# BMS_Schematic.net
KiCad netlist of a schematic drawn in EAGLE
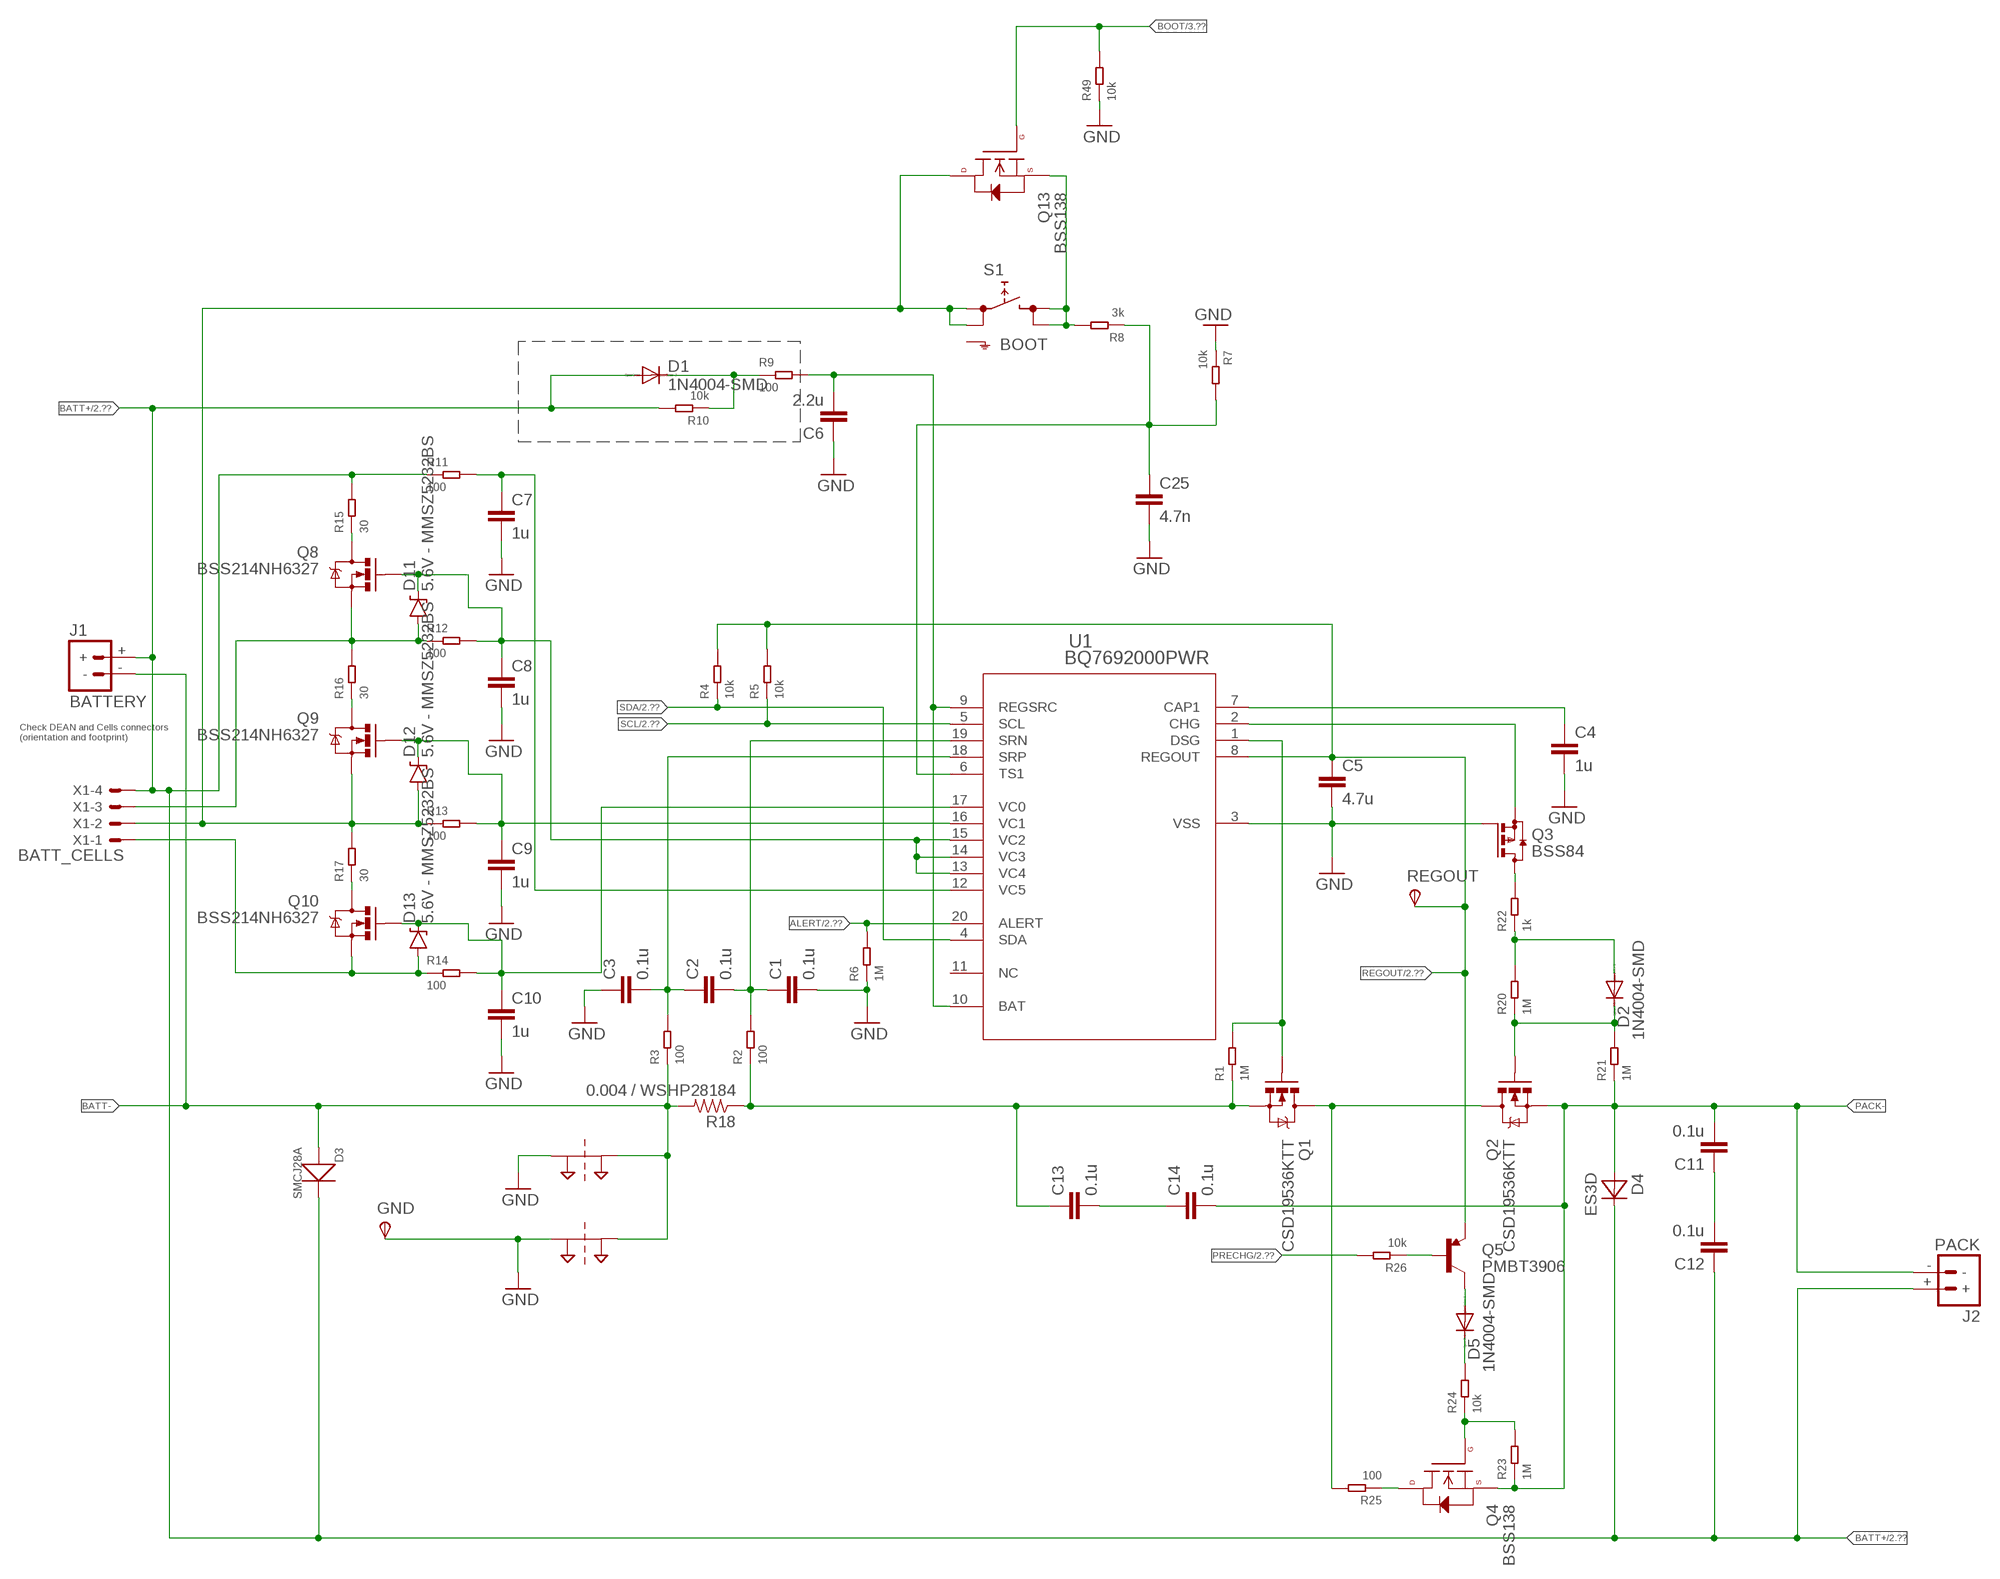
[diagram p0: schematic, sheet 1]
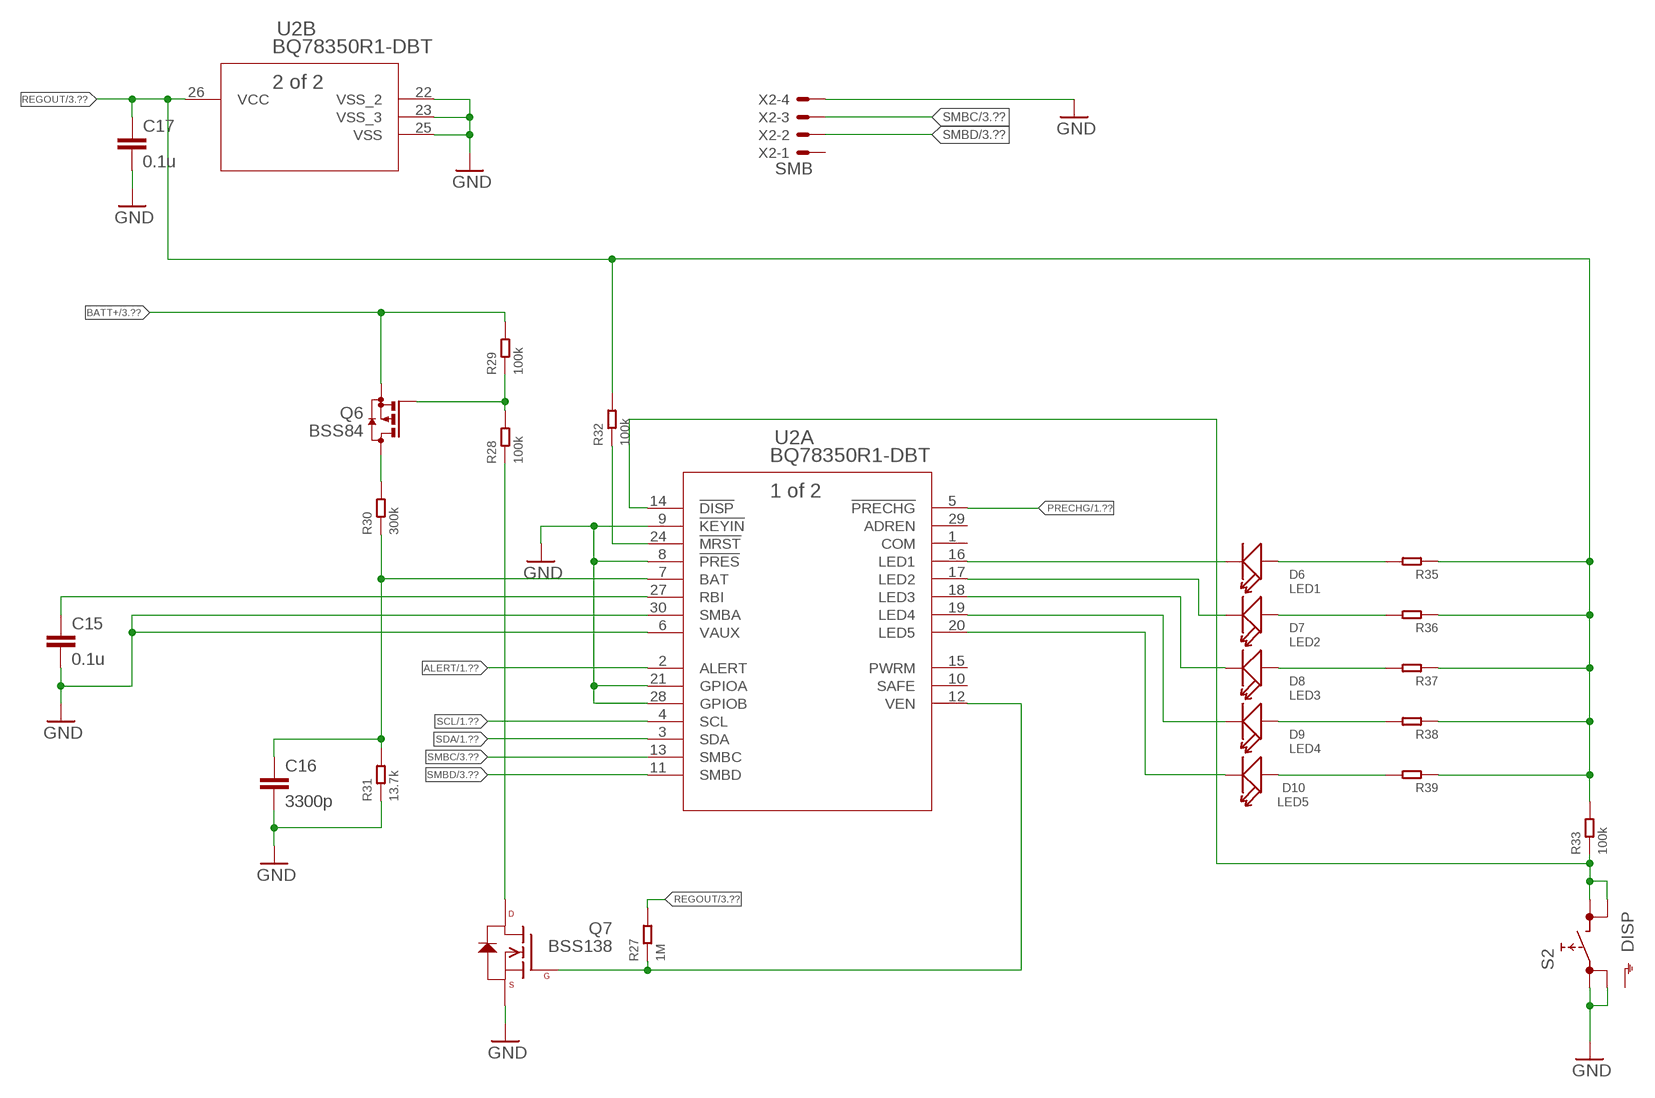
[diagram p1: schematic, sheet 2]
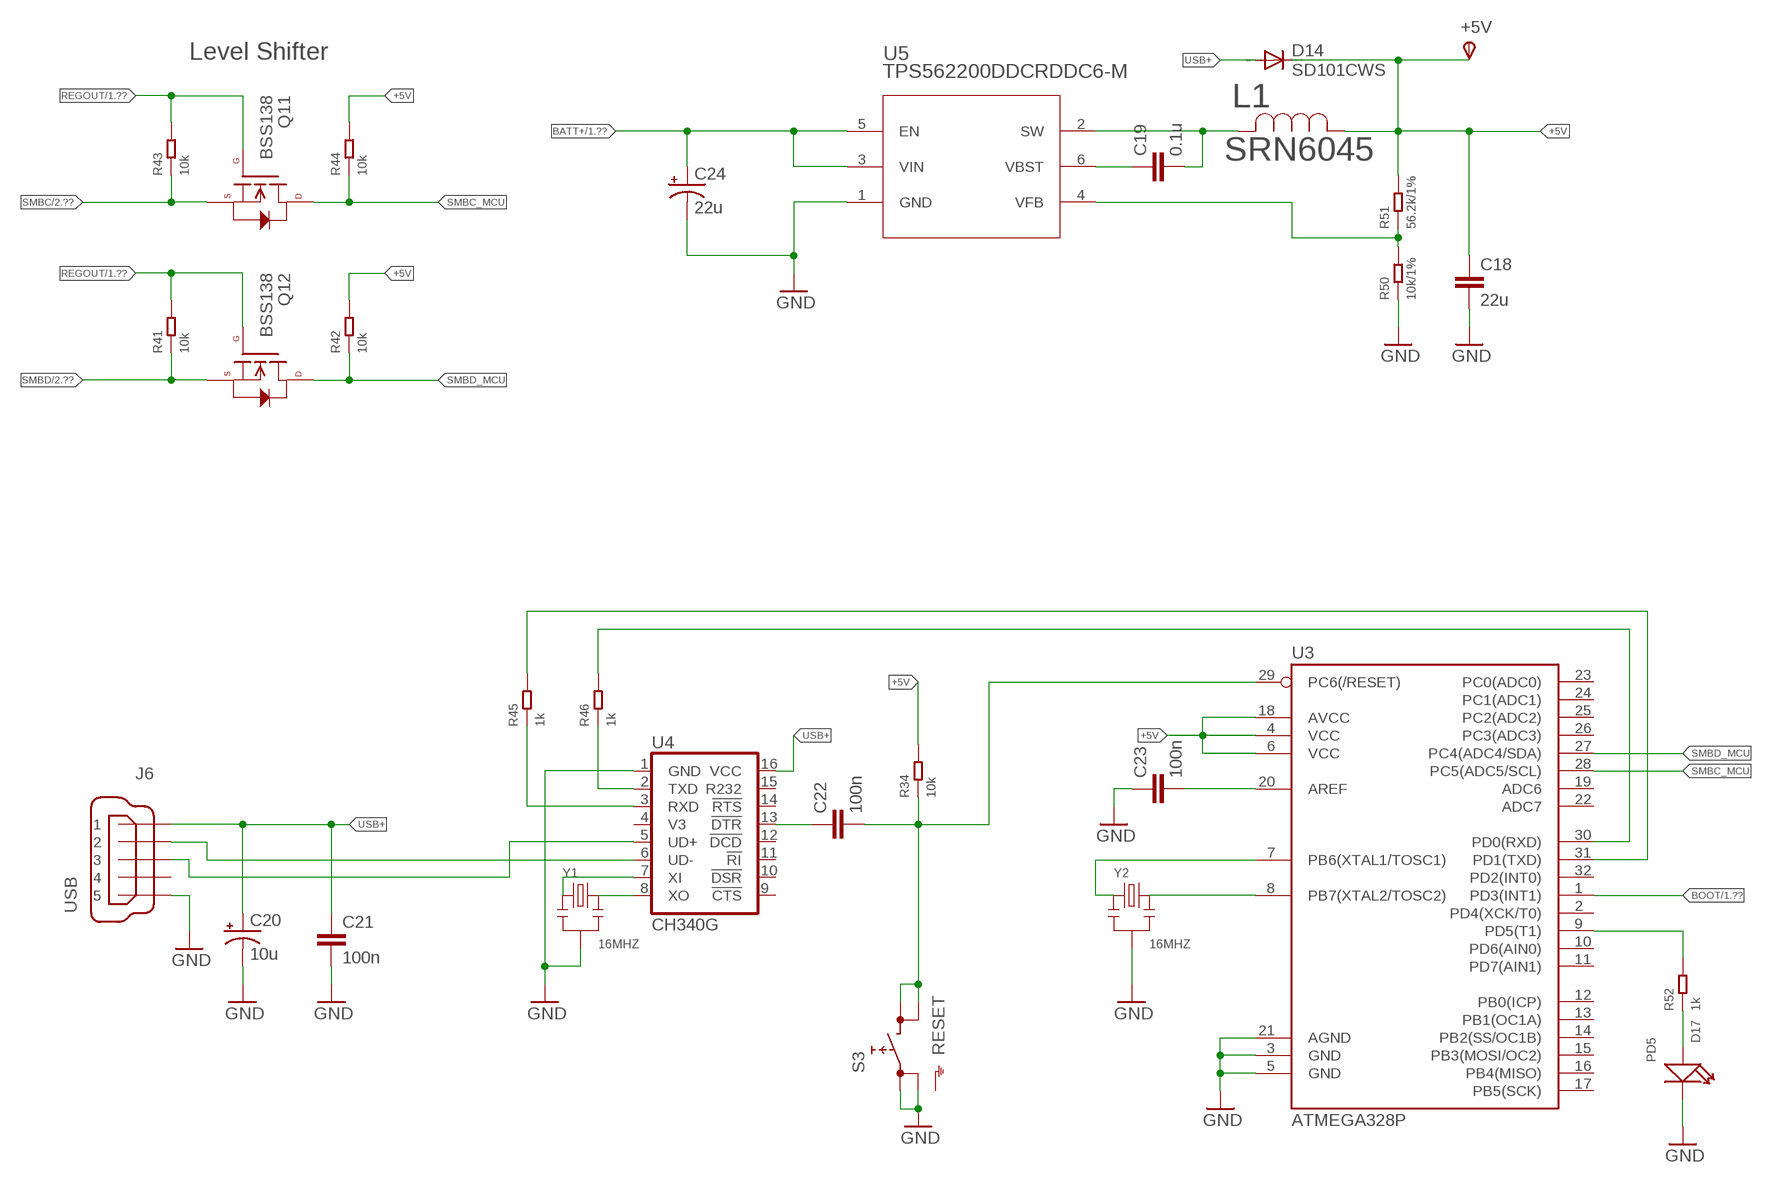
[diagram p2: schematic, sheet 3]

(export (version "E")
  (design (tool "Eeschema 10.0.6"))
  (components
    (comp (ref "C1")
      (value "0.1u")
      (footprint "eagle-import:0805")
      (libsource (lib "eagle-import") (part "CAP0805"))
    )
    (comp (ref "C2")
      (value "0.1u")
      (footprint "eagle-import:0805")
      (libsource (lib "eagle-import") (part "CAP0805"))
    )
    (comp (ref "C3")
      (value "0.1u")
      (footprint "eagle-import:0805")
      (libsource (lib "eagle-import") (part "CAP0805"))
    )
    (comp (ref "C4")
      (value "1u")
      (footprint "eagle-import:0805")
      (libsource (lib "eagle-import") (part "CAP0805"))
    )
    (comp (ref "C5")
      (value "4.7u")
      (footprint "eagle-import:0805")
      (libsource (lib "eagle-import") (part "CAP0805"))
    )
    (comp (ref "C6")
      (value "2.2u")
      (footprint "eagle-import:C1206")
      (libsource (lib "eagle-import") (part "C-EUC1206"))
    )
    (comp (ref "C7")
      (value "1u")
      (footprint "eagle-import:0805")
      (libsource (lib "eagle-import") (part "CAP0805"))
    )
    (comp (ref "C8")
      (value "1u")
      (footprint "eagle-import:0805")
      (libsource (lib "eagle-import") (part "CAP0805"))
    )
    (comp (ref "C9")
      (value "1u")
      (footprint "eagle-import:0805")
      (libsource (lib "eagle-import") (part "CAP0805"))
    )
    (comp (ref "C10")
      (value "1u")
      (footprint "eagle-import:0805")
      (libsource (lib "eagle-import") (part "CAP0805"))
    )
    (comp (ref "C11")
      (value "0.1u")
      (footprint "eagle-import:0805")
      (libsource (lib "eagle-import") (part "CAP0805"))
    )
    (comp (ref "C12")
      (value "0.1u")
      (footprint "eagle-import:0805")
      (libsource (lib "eagle-import") (part "CAP0805"))
    )
    (comp (ref "C13")
      (value "0.1u")
      (footprint "eagle-import:0805")
      (libsource (lib "eagle-import") (part "CAP0805"))
    )
    (comp (ref "C14")
      (value "0.1u")
      (footprint "eagle-import:0805")
      (libsource (lib "eagle-import") (part "CAP0805"))
    )
    (comp (ref "C25")
      (value "4.7n")
      (footprint "eagle-import:0805")
      (libsource (lib "eagle-import") (part "CAP0805"))
    )
    (comp (ref "D1")
      (value "1N4004-SMD")
      (footprint "eagle-import:DO-214")
      (libsource (lib "eagle-import") (part "1N4004-SMD"))
    )
    (comp (ref "D2")
      (value "1N4004-SMD")
      (footprint "eagle-import:DO-214")
      (libsource (lib "eagle-import") (part "1N4004-SMD"))
    )
    (comp (ref "D3")
      (value "SMCJ28A")
      (footprint "eagle-import:DO-214AB")
      (fields (field (name "MPN") "SS34-E3/57T"))
      (libsource (lib "eagle-import") (part "SMD-DIODE-SCHOTTKY-40V-3A(DO-214AB)"))
    )
    (comp (ref "D4")
      (value "ES3D")
      (footprint "eagle-import:SMC")
      (libsource (lib "eagle-import") (part "ES3D"))
    )
    (comp (ref "D5")
      (value "1N4004-SMD")
      (footprint "eagle-import:DO-214")
      (libsource (lib "eagle-import") (part "1N4004-SMD"))
    )
    (comp (ref "D11")
      (value "5.6V - MMSZ5232BS")
      (footprint "eagle-import:SOD-323")
      (libsource (lib "eagle-import") (part "DIODE-ZENER5.6V"))
    )
    (comp (ref "D12")
      (value "5.6V - MMSZ5232BS")
      (footprint "eagle-import:SOD-323")
      (libsource (lib "eagle-import") (part "DIODE-ZENER5.6V"))
    )
    (comp (ref "D13")
      (value "5.6V - MMSZ5232BS")
      (footprint "eagle-import:SOD-323")
      (libsource (lib "eagle-import") (part "DIODE-ZENER5.6V"))
    )
    (comp (ref "GND")
      (value "GND")
      (footprint "eagle-import:P1-17")
      (fields (field (name "SPICEPREFIX") "X"))
      (libsource (lib "eagle-import") (part "TPSPAD1-17"))
    )
    (comp (ref "J1")
      (value "BATTERY")
      (footprint "eagle-import:DEANS")
      (libsource (lib "eagle-import") (part "BATTERY_CONN_DEANS"))
    )
    (comp (ref "J2")
      (value "PACK")
      (footprint "eagle-import:DEANS")
      (libsource (lib "eagle-import") (part "BATTERY_CONN_DEANS"))
    )
    (comp (ref "PT1")
      (value "2PT_GND_TIE")
      (footprint "eagle-import:2PT_GND_TIE")
      (libsource (lib "eagle-import") (part "2PT_GND_TIE"))
    )
    (comp (ref "PT2")
      (value "2PT_GND_TIE")
      (footprint "eagle-import:2PT_GND_TIE")
      (libsource (lib "eagle-import") (part "2PT_GND_TIE"))
    )
    (comp (ref "Q1")
      (value "CSD19536KTT")
      (footprint "eagle-import:TO-263_D2PAK")
      (libsource (lib "eagle-import") (part "MOSFET-NCHANNELPSMN7R0"))
    )
    (comp (ref "Q2")
      (value "CSD19536KTT")
      (footprint "eagle-import:TO-263_D2PAK")
      (libsource (lib "eagle-import") (part "MOSFET-NCHANNELPSMN7R0"))
    )
    (comp (ref "Q3")
      (value "BSS84")
      (footprint "eagle-import:SOT23")
      (libsource (lib "eagle-import") (part "BSS84"))
    )
    (comp (ref "Q4")
      (value "BSS138")
      (footprint "eagle-import:SOT23-3")
      (libsource (lib "eagle-import") (part "N-CHANNEL-MOSFET-BSS138"))
    )
    (comp (ref "Q5")
      (value "PMBT3906")
      (footprint "eagle-import:SOT23-3")
      (libsource (lib "eagle-import") (part "TRANSISTOR_PNPPMBT3906"))
    )
    (comp (ref "Q8")
      (value "BSS214NH6327")
      (footprint "eagle-import:SOT23-3")
      (libsource (lib "eagle-import") (part "MOSFET-NCHANNELBSS138"))
    )
    (comp (ref "Q9")
      (value "BSS214NH6327")
      (footprint "eagle-import:SOT23-3")
      (libsource (lib "eagle-import") (part "MOSFET-NCHANNELBSS138"))
    )
    (comp (ref "Q10")
      (value "BSS214NH6327")
      (footprint "eagle-import:SOT23-3")
      (libsource (lib "eagle-import") (part "MOSFET-NCHANNELBSS138"))
    )
    (comp (ref "Q13")
      (value "BSS138")
      (footprint "eagle-import:SOT23-3")
      (libsource (lib "eagle-import") (part "N-CHANNEL-MOSFET-BSS138"))
    )
    (comp (ref "R1")
      (value "1M")
      (footprint "eagle-import:R0805")
      (libsource (lib "eagle-import") (part "RES-0805"))
    )
    (comp (ref "R2")
      (value "100")
      (footprint "eagle-import:R0805")
      (libsource (lib "eagle-import") (part "RES-0805"))
    )
    (comp (ref "R3")
      (value "100")
      (footprint "eagle-import:R0805")
      (libsource (lib "eagle-import") (part "RES-0805"))
    )
    (comp (ref "R4")
      (value "10k")
      (footprint "eagle-import:R0805")
      (libsource (lib "eagle-import") (part "RES-0805"))
    )
    (comp (ref "R5")
      (value "10k")
      (footprint "eagle-import:R0805")
      (libsource (lib "eagle-import") (part "RES-0805"))
    )
    (comp (ref "R6")
      (value "1M")
      (footprint "eagle-import:R0805")
      (libsource (lib "eagle-import") (part "RES-0805"))
    )
    (comp (ref "R7")
      (value "10k")
      (footprint "eagle-import:R0805")
      (libsource (lib "eagle-import") (part "RES-0805"))
    )
    (comp (ref "R8")
      (value "3k")
      (footprint "eagle-import:R0805")
      (libsource (lib "eagle-import") (part "RES-0805"))
    )
    (comp (ref "R9")
      (value "100")
      (footprint "eagle-import:R0805")
      (libsource (lib "eagle-import") (part "RES-0805"))
    )
    (comp (ref "R10")
      (value "10k")
      (footprint "eagle-import:R0805")
      (libsource (lib "eagle-import") (part "RES-0805"))
    )
    (comp (ref "R11")
      (value "100")
      (footprint "eagle-import:R0805")
      (libsource (lib "eagle-import") (part "RES-0805"))
    )
    (comp (ref "R12")
      (value "100")
      (footprint "eagle-import:R0805")
      (libsource (lib "eagle-import") (part "RES-0805"))
    )
    (comp (ref "R13")
      (value "100")
      (footprint "eagle-import:R0805")
      (libsource (lib "eagle-import") (part "RES-0805"))
    )
    (comp (ref "R14")
      (value "100")
      (footprint "eagle-import:R0805")
      (libsource (lib "eagle-import") (part "RES-0805"))
    )
    (comp (ref "R15")
      (value "30")
      (footprint "eagle-import:R2512")
      (libsource (lib "eagle-import") (part "RES-2512"))
    )
    (comp (ref "R16")
      (value "30")
      (footprint "eagle-import:R2512")
      (libsource (lib "eagle-import") (part "RES-2512"))
    )
    (comp (ref "R17")
      (value "30")
      (footprint "eagle-import:R2512")
      (libsource (lib "eagle-import") (part "RES-2512"))
    )
    (comp (ref "R18")
      (value "0.004 / WSHP28184")
      (footprint "eagle-import:2512")
      (libsource (lib "eagle-import") (part "0.001OHM-3W-1%(2512)3W/1%"))
    )
    (comp (ref "R20")
      (value "1M")
      (footprint "eagle-import:R0805")
      (libsource (lib "eagle-import") (part "RES-0805"))
    )
    (comp (ref "R21")
      (value "1M")
      (footprint "eagle-import:R0805")
      (libsource (lib "eagle-import") (part "RES-0805"))
    )
    (comp (ref "R22")
      (value "1k")
      (footprint "eagle-import:R0805")
      (libsource (lib "eagle-import") (part "RES-0805"))
    )
    (comp (ref "R23")
      (value "1M")
      (footprint "eagle-import:R0805")
      (libsource (lib "eagle-import") (part "RES-0805"))
    )
    (comp (ref "R24")
      (value "10k")
      (footprint "eagle-import:R0805")
      (libsource (lib "eagle-import") (part "RES-0805"))
    )
    (comp (ref "R25")
      (value "100")
      (footprint "eagle-import:R2512")
      (libsource (lib "eagle-import") (part "RES-2512"))
    )
    (comp (ref "R26")
      (value "10k")
      (footprint "eagle-import:R0805")
      (libsource (lib "eagle-import") (part "RES-0805"))
    )
    (comp (ref "R49")
      (value "10k")
      (footprint "eagle-import:R0805")
      (libsource (lib "eagle-import") (part "RES-0805"))
    )
    (comp (ref "REGOUT")
      (value "TPSB2,54")
      (footprint "eagle-import:B2,54")
      (libsource (lib "eagle-import") (part "TPSB2,54"))
    )
    (comp (ref "S1")
      (value "BOOT")
      (footprint "eagle-import:SKHMPXE010")
      (libsource (lib "eagle-import") (part "SKHMPE010S"))
    )
    (comp (ref "U1")
      (value "BQ7692000PWR")
      (footprint "eagle-import:PW20")
      (fields (field (name "MANUFACTURER_PART_NUMBER") "BQ7692006PWR"))
      (libsource (lib "eagle-import") (part "BQ7692006PWR"))
    )
    (comp (ref "X1")
      (value "BATT_CELLS")
      (footprint "eagle-import:70543-04")
      (libsource (lib "eagle-import") (part "C-GRID-04-70543"))
    )
    (comp (ref "+5V")
      (value "TPSB2,54")
      (footprint "eagle-import:B2,54")
      (libsource (lib "eagle-import") (part "TPSB2,54"))
    )
    (comp (ref "C18")
      (value "22u")
      (footprint "eagle-import:0805")
      (libsource (lib "eagle-import") (part "CAP0805"))
    )
    (comp (ref "C19")
      (value "0.1u")
      (footprint "eagle-import:0805")
      (libsource (lib "eagle-import") (part "CAP0805"))
    )
    (comp (ref "C20")
      (value "10u")
      (footprint "eagle-import:EIA3216-KIT")
      (libsource (lib "eagle-import") (part "CAP_POL1206-KIT"))
    )
    (comp (ref "C21")
      (value "100n")
      (footprint "eagle-import:0603-CAP")
      (libsource (lib "eagle-import") (part "CAP0603-CAP"))
    )
    (comp (ref "C22")
      (value "100n")
      (footprint "eagle-import:0603-CAP")
      (libsource (lib "eagle-import") (part "CAP0603-CAP"))
    )
    (comp (ref "C23")
      (value "100n")
      (footprint "eagle-import:0603-CAP")
      (libsource (lib "eagle-import") (part "CAP0603-CAP"))
    )
    (comp (ref "C24")
      (value "22u")
      (footprint "eagle-import:PANASONIC_C")
      (libsource (lib "eagle-import") (part "CAP_POLC"))
    )
    (comp (ref "D14")
      (value "SD101CWS")
      (footprint "eagle-import:SOD323-W")
      (libsource (lib "eagle-import") (part "DIODE-SOD323-W"))
    )
    (comp (ref "D17")
      (value "PD5")
      (footprint "eagle-import:LED-0805")
      (fields (field (name "MPN") "17-215SYGC/S530-E2/TR8"))
      (libsource (lib "eagle-import") (part "SMD-LED-CLEAR-GREEN(0805)"))
    )
    (comp (ref "J6")
      (value "USB")
      (footprint "eagle-import:USB-MINI-B_2")
      (libsource (lib "eagle-import") (part "MINI-USB-ARDUINO-NANO"))
    )
    (comp (ref "L1")
      (value "SRN6045")
      (footprint "eagle-import:IND_BOURNS_SRN6045")
      (libsource (lib "eagle-import") (part "BOURNS_SRN6045"))
    )
    (comp (ref "Q11")
      (value "BSS138")
      (footprint "eagle-import:SOT23-3")
      (libsource (lib "eagle-import") (part "N-CHANNEL-MOSFET-BSS138"))
    )
    (comp (ref "Q12")
      (value "BSS138")
      (footprint "eagle-import:SOT23-3")
      (libsource (lib "eagle-import") (part "N-CHANNEL-MOSFET-BSS138"))
    )
    (comp (ref "R34")
      (value "10k")
      (footprint "eagle-import:R0805")
      (libsource (lib "eagle-import") (part "RES-0805"))
    )
    (comp (ref "R41")
      (value "10k")
      (footprint "eagle-import:R0805")
      (libsource (lib "eagle-import") (part "RES-0805"))
    )
    (comp (ref "R42")
      (value "10k")
      (footprint "eagle-import:R0805")
      (libsource (lib "eagle-import") (part "RES-0805"))
    )
    (comp (ref "R43")
      (value "10k")
      (footprint "eagle-import:R0805")
      (libsource (lib "eagle-import") (part "RES-0805"))
    )
    (comp (ref "R44")
      (value "10k")
      (footprint "eagle-import:R0805")
      (libsource (lib "eagle-import") (part "RES-0805"))
    )
    (comp (ref "R45")
      (value "1k")
      (footprint "eagle-import:R0805")
      (libsource (lib "eagle-import") (part "RES-0805"))
    )
    (comp (ref "R46")
      (value "1k")
      (footprint "eagle-import:R0805")
      (libsource (lib "eagle-import") (part "RES-0805"))
    )
    (comp (ref "R50")
      (value "10k/1%")
      (footprint "eagle-import:R0805")
      (libsource (lib "eagle-import") (part "RES-0805"))
    )
    (comp (ref "R51")
      (value "56.2k/1%")
      (footprint "eagle-import:R0805")
      (libsource (lib "eagle-import") (part "RES-0805"))
    )
    (comp (ref "R52")
      (value "1k")
      (footprint "eagle-import:R0805")
      (libsource (lib "eagle-import") (part "RES-0805"))
    )
    (comp (ref "S3")
      (value "RESET")
      (footprint "eagle-import:SKHMPXE010")
      (libsource (lib "eagle-import") (part "SKHMPE010S"))
    )
    (comp (ref "U3")
      (value "ATMEGA328P")
      (footprint "eagle-import:TQFP32-08")
      (libsource (lib "eagle-import") (part "ATMEGA328P_TQFP"))
    )
    (comp (ref "U4")
      (value "CH340G")
      (footprint "eagle-import:SO016")
      (libsource (lib "eagle-import") (part "CH340GSMD"))
    )
    (comp (ref "U5")
      (value "TPS562200DDCRDDC6-M")
      (footprint "eagle-import:DDC6-M")
      (fields (field (name "MANUFACTURER_PART_NUMBER") "TPS562200DDCR"))
      (libsource (lib "eagle-import") (part "TPS562200DDCRDDC6-M"))
    )
    (comp (ref "Y1")
      (value "16MHZ")
      (footprint "eagle-import:X3-SMD-3.6X1.3X0.8MM")
      (fields (field (name "MPN") "CSTCE16M0V53-R0"))
      (libsource (lib "eagle-import") (part "SMD-RESONATOR-16MHZ-15PF-0.5%-40R(3P-3.2X1.3MM)"))
    )
    (comp (ref "Y2")
      (value "16MHZ")
      (footprint "eagle-import:X3-SMD-3.6X1.3X0.8MM")
      (fields (field (name "MPN") "CSTCE16M0V53-R0"))
      (libsource (lib "eagle-import") (part "SMD-RESONATOR-16MHZ-15PF-0.5%-40R(3P-3.2X1.3MM)"))
    )
    (comp (ref "C15")
      (value "0.1u")
      (footprint "eagle-import:0805")
      (libsource (lib "eagle-import") (part "CAP0805"))
    )
    (comp (ref "C16")
      (value "3300p")
      (footprint "eagle-import:0805")
      (libsource (lib "eagle-import") (part "CAP0805"))
    )
    (comp (ref "C17")
      (value "0.1u")
      (footprint "eagle-import:0805")
      (libsource (lib "eagle-import") (part "CAP0805"))
    )
    (comp (ref "D6")
      (value "LED1")
      (footprint "eagle-import:LED-0805")
      (fields (field (name "MPN") "17-215SYGC/S530-E2/TR8"))
      (libsource (lib "eagle-import") (part "SMD-LED-CLEAR-GREEN(0805)"))
    )
    (comp (ref "D7")
      (value "LED2")
      (footprint "eagle-import:LED-0805")
      (fields (field (name "MPN") "17-215SYGC/S530-E2/TR8"))
      (libsource (lib "eagle-import") (part "SMD-LED-CLEAR-GREEN(0805)"))
    )
    (comp (ref "D8")
      (value "LED3")
      (footprint "eagle-import:LED-0805")
      (fields (field (name "MPN") "17-215SYGC/S530-E2/TR8"))
      (libsource (lib "eagle-import") (part "SMD-LED-CLEAR-GREEN(0805)"))
    )
    (comp (ref "D9")
      (value "LED4")
      (footprint "eagle-import:LED-0805")
      (fields (field (name "MPN") "17-215SYGC/S530-E2/TR8"))
      (libsource (lib "eagle-import") (part "SMD-LED-CLEAR-GREEN(0805)"))
    )
    (comp (ref "D10")
      (value "LED5")
      (footprint "eagle-import:LED-0805")
      (fields (field (name "MPN") "17-215SURC/S530-A2/TR8"))
      (libsource (lib "eagle-import") (part "SMD-LED-CLEAR-RED(0805)"))
    )
    (comp (ref "Q6")
      (value "BSS84")
      (footprint "eagle-import:SOT23")
      (libsource (lib "eagle-import") (part "BSS84"))
    )
    (comp (ref "Q7")
      (value "BSS138")
      (footprint "eagle-import:SOT23-3")
      (libsource (lib "eagle-import") (part "N-CHANNEL-MOSFET-BSS138"))
    )
    (comp (ref "R27")
      (value "1M")
      (footprint "eagle-import:R0805")
      (libsource (lib "eagle-import") (part "RES-0805"))
    )
    (comp (ref "R28")
      (value "100k")
      (footprint "eagle-import:R0805")
      (libsource (lib "eagle-import") (part "RES-0805"))
    )
    (comp (ref "R29")
      (value "100k")
      (footprint "eagle-import:R0805")
      (libsource (lib "eagle-import") (part "RES-0805"))
    )
    (comp (ref "R30")
      (value "300k")
      (footprint "eagle-import:R0805")
      (libsource (lib "eagle-import") (part "RES-0805"))
    )
    (comp (ref "R31")
      (value "13.7k")
      (footprint "eagle-import:R0805")
      (libsource (lib "eagle-import") (part "RES-0805"))
    )
    (comp (ref "R32")
      (value "100k")
      (footprint "eagle-import:R0805")
      (libsource (lib "eagle-import") (part "RES-0805"))
    )
    (comp (ref "R33")
      (value "100k")
      (footprint "eagle-import:R0805")
      (libsource (lib "eagle-import") (part "RES-0805"))
    )
    (comp (ref "R35")
      (value "RES-0805")
      (footprint "eagle-import:R0805")
      (libsource (lib "eagle-import") (part "RES-0805"))
    )
    (comp (ref "R36")
      (value "RES-0805")
      (footprint "eagle-import:R0805")
      (libsource (lib "eagle-import") (part "RES-0805"))
    )
    (comp (ref "R37")
      (value "RES-0805")
      (footprint "eagle-import:R0805")
      (libsource (lib "eagle-import") (part "RES-0805"))
    )
    (comp (ref "R38")
      (value "RES-0805")
      (footprint "eagle-import:R0805")
      (libsource (lib "eagle-import") (part "RES-0805"))
    )
    (comp (ref "R39")
      (value "RES-0805")
      (footprint "eagle-import:R0805")
      (libsource (lib "eagle-import") (part "RES-0805"))
    )
    (comp (ref "S2")
      (value "DISP")
      (footprint "eagle-import:SKHMPXE010")
      (libsource (lib "eagle-import") (part "SKHMPE010S"))
    )
    (comp (ref "U2")
      (value "BQ78350R1-DBT")
      (footprint "eagle-import:DBT30")
      (fields (field (name "MANUFACTURER_PART_NUMBER") "BQ78350DBT"))
      (libsource (lib "eagle-import") (part "BQ78350R1-DBT"))
    )
    (comp (ref "X2")
      (value "SMB")
      (footprint "eagle-import:70543-04")
      (libsource (lib "eagle-import") (part "C-GRID-04-70543"))
    )
  )
  (nets
    (net (code "1") (name "+5V") (class "Default")
      (node (ref "+5V") (pin "TP") (pinfunction "PP_TP") (pintype "input"))
      (node (ref "C18") (pin "1") (pinfunction "1_1") (pintype "passive"))
      (node (ref "D14") (pin "C") (pinfunction "C_C") (pintype "passive"))
      (node (ref "L1") (pin "1") (pinfunction "1_1") (pintype "passive"))
      (node (ref "R34") (pin "2") (pinfunction "2_2") (pintype "passive"))
      (node (ref "R42") (pin "2") (pinfunction "2_2") (pintype "passive"))
      (node (ref "R44") (pin "2") (pinfunction "2_2") (pintype "passive"))
      (node (ref "R51") (pin "2") (pinfunction "2_2") (pintype "passive"))
      (node (ref "U3") (pin "18") (pinfunction "AVCC_18") (pintype "bidirectional"))
      (node (ref "U3") (pin "4") (pinfunction "VCC_4") (pintype "bidirectional"))
      (node (ref "U3") (pin "6") (pinfunction "VCC_6") (pintype "bidirectional"))
    )
    (net (code "2") (name "ALERT") (class "Default")
      (node (ref "R6") (pin "2") (pinfunction "2_2") (pintype "passive"))
      (node (ref "U1") (pin "20") (pinfunction "ALERT_20") (pintype "bidirectional"))
      (node (ref "U2") (pin "2") (pinfunction "ALERT_2") (pintype "bidirectional"))
    )
    (net (code "3") (name "BATT+") (class "Default")
      (node (ref "C12") (pin "1") (pinfunction "1_1") (pintype "passive"))
      (node (ref "C24") (pin "+") (pinfunction "+_+") (pintype "passive"))
      (node (ref "D1") (pin "A") (pinfunction "A_A") (pintype "passive"))
      (node (ref "D3") (pin "2") (pinfunction "-_2") (pintype "passive"))
      (node (ref "D4") (pin "C") (pinfunction "C_C") (pintype "passive"))
      (node (ref "J1") (pin "+") (pinfunction "+_+") (pintype "passive"))
      (node (ref "J2") (pin "+") (pinfunction "+_+") (pintype "passive"))
      (node (ref "Q6") (pin "2") (pinfunction "S_2") (pintype "passive"))
      (node (ref "R10") (pin "2") (pinfunction "2_2") (pintype "passive"))
      (node (ref "R11") (pin "1") (pinfunction "1_1") (pintype "passive"))
      (node (ref "R15") (pin "2") (pinfunction "2_2") (pintype "passive"))
      (node (ref "R29") (pin "2") (pinfunction "2_2") (pintype "passive"))
      (node (ref "U5") (pin "3") (pinfunction "VIN_3") (pintype "input"))
      (node (ref "U5") (pin "5") (pinfunction "EN_5") (pintype "input"))
      (node (ref "X1") (pin "4") (pinfunction "S_4") (pintype "passive"))
    )
    (net (code "4") (name "BATT-") (class "Default")
      (node (ref "D3") (pin "1") (pinfunction "+_1") (pintype "passive"))
      (node (ref "J1") (pin "-") (pinfunction "-_-") (pintype "passive"))
      (node (ref "PT1") (pin "P$2") (pinfunction "P$2_P$2") (pintype "bidirectional"))
      (node (ref "PT2") (pin "P$2") (pinfunction "P$2_P$2") (pintype "bidirectional"))
      (node (ref "R18") (pin "2") (pinfunction "2_2") (pintype "passive"))
      (node (ref "R3") (pin "1") (pinfunction "1_1") (pintype "passive"))
    )
    (net (code "5") (name "BOOT") (class "Default")
      (node (ref "Q13") (pin "1") (pinfunction "G_1") (pintype "passive"))
      (node (ref "R49") (pin "2") (pinfunction "2_2") (pintype "passive"))
      (node (ref "U3") (pin "1") (pinfunction "PD3(INT1)_1") (pintype "bidirectional"))
    )
    (net (code "6") (name "GND") (class "Default")
      (node (ref "C1") (pin "2") (pinfunction "2_2") (pintype "passive"))
      (node (ref "C10") (pin "2") (pinfunction "2_2") (pintype "passive"))
      (node (ref "C15") (pin "2") (pinfunction "2_2") (pintype "passive"))
      (node (ref "C16") (pin "2") (pinfunction "2_2") (pintype "passive"))
      (node (ref "C17") (pin "2") (pinfunction "2_2") (pintype "passive"))
      (node (ref "C18") (pin "2") (pinfunction "2_2") (pintype "passive"))
      (node (ref "C20") (pin "C") (pinfunction "-_C") (pintype "passive"))
      (node (ref "C21") (pin "2") (pinfunction "2_2") (pintype "passive"))
      (node (ref "C23") (pin "1") (pinfunction "1_1") (pintype "passive"))
      (node (ref "C24") (pin "-") (pinfunction "-_-") (pintype "passive"))
      (node (ref "C25") (pin "2") (pinfunction "2_2") (pintype "passive"))
      (node (ref "C3") (pin "1") (pinfunction "1_1") (pintype "passive"))
      (node (ref "C4") (pin "2") (pinfunction "2_2") (pintype "passive"))
      (node (ref "C5") (pin "2") (pinfunction "2_2") (pintype "passive"))
      (node (ref "C6") (pin "1") (pinfunction "1_1") (pintype "passive"))
      (node (ref "C7") (pin "2") (pinfunction "2_2") (pintype "passive"))
      (node (ref "C8") (pin "2") (pinfunction "2_2") (pintype "passive"))
      (node (ref "C9") (pin "2") (pinfunction "2_2") (pintype "passive"))
      (node (ref "D17") (pin "-") (pinfunction "-_-") (pintype "passive"))
      (node (ref "GND") (pin "TP") (pinfunction "PP_TP") (pintype "input"))
      (node (ref "J6") (pin "1") (pinfunction "5_1") (pintype "passive"))
      (node (ref "PT1") (pin "P$1") (pinfunction "P$1_P$1") (pintype "bidirectional"))
      (node (ref "PT2") (pin "P$1") (pinfunction "P$1_P$1") (pintype "bidirectional"))
      (node (ref "Q3") (pin "1") (pinfunction "G_1") (pintype "passive"))
      (node (ref "Q7") (pin "2") (pinfunction "S_2") (pintype "passive"))
      (node (ref "R31") (pin "1") (pinfunction "1_1") (pintype "passive"))
      (node (ref "R49") (pin "1") (pinfunction "1_1") (pintype "passive"))
      (node (ref "R50") (pin "1") (pinfunction "1_1") (pintype "passive"))
      (node (ref "R6") (pin "1") (pinfunction "1_1") (pintype "passive"))
      (node (ref "R7") (pin "1") (pinfunction "1_1") (pintype "passive"))
      (node (ref "S2") (pin "1") (pinfunction "1.1_1") (pintype "passive"))
      (node (ref "S2") (pin "2") (pinfunction "1.2_2") (pintype "passive"))
      (node (ref "S3") (pin "1") (pinfunction "1.1_1") (pintype "passive"))
      (node (ref "S3") (pin "2") (pinfunction "1.2_2") (pintype "passive"))
      (node (ref "U1") (pin "3") (pinfunction "VSS_3") (pintype "power_in"))
      (node (ref "U2") (pin "21") (pinfunction "GPIOA_21") (pintype "bidirectional"))
      (node (ref "U2") (pin "22") (pinfunction "VSS_2_22") (pintype "power_in"))
      (node (ref "U2") (pin "23") (pinfunction "VSS_3_23") (pintype "power_in"))
      (node (ref "U2") (pin "25") (pinfunction "VSS_25") (pintype "power_in"))
      (node (ref "U2") (pin "28") (pinfunction "GPIOB_28") (pintype "bidirectional"))
      (node (ref "U2") (pin "30") (pinfunction "SMBA_30") (pintype "input"))
      (node (ref "U2") (pin "6") (pinfunction "VAUX_6") (pintype "input"))
      (node (ref "U2") (pin "8") (pinfunction "~{PRES}_8") (pintype "input"))
      (node (ref "U2") (pin "9") (pinfunction "~{KEYIN}_9") (pintype "input"))
      (node (ref "U3") (pin "21") (pinfunction "AGND_21") (pintype "bidirectional"))
      (node (ref "U3") (pin "3") (pinfunction "GND_3") (pintype "bidirectional"))
      (node (ref "U3") (pin "5") (pinfunction "GND_5") (pintype "bidirectional"))
      (node (ref "U4") (pin "1") (pinfunction "GND_1") (pintype "bidirectional"))
      (node (ref "U5") (pin "1") (pinfunction "GND_1") (pintype "power_in"))
      (node (ref "X2") (pin "4") (pinfunction "S_4") (pintype "passive"))
      (node (ref "Y1") (pin "2") (pinfunction "2_2") (pintype "passive"))
      (node (ref "Y2") (pin "2") (pinfunction "2_2") (pintype "passive"))
    )
    (net (code "7") (name "Net-(C11-Pad1)") (class "Default")
      (node (ref "C11") (pin "1") (pinfunction "1_1") (pintype "passive"))
      (node (ref "C12") (pin "2") (pinfunction "2_2") (pintype "passive"))
    )
    (net (code "8") (name "Net-(C13-Pad2)") (class "Default")
      (node (ref "C13") (pin "2") (pinfunction "2_2") (pintype "passive"))
      (node (ref "C14") (pin "1") (pinfunction "1_1") (pintype "passive"))
    )
    (net (code "9") (name "Net-(D1-PadC)") (class "Default")
      (node (ref "D1") (pin "C") (pinfunction "C_C") (pintype "passive"))
      (node (ref "R10") (pin "1") (pinfunction "1_1") (pintype "passive"))
      (node (ref "R9") (pin "1") (pinfunction "1_1") (pintype "passive"))
    )
    (net (code "10") (name "Net-(D2-PadA)") (class "Default")
      (node (ref "D2") (pin "A") (pinfunction "A_A") (pintype "passive"))
      (node (ref "R20") (pin "2") (pinfunction "2_2") (pintype "passive"))
      (node (ref "R22") (pin "1") (pinfunction "1_1") (pintype "passive"))
    )
    (net (code "11") (name "Net-(D5-PadC)") (class "Default")
      (node (ref "D5") (pin "C") (pinfunction "C_C") (pintype "passive"))
      (node (ref "R24") (pin "2") (pinfunction "2_2") (pintype "passive"))
    )
    (net (code "12") (name "Net-(D6-Pad+)") (class "Default")
      (node (ref "D6") (pin "+") (pinfunction "+_+") (pintype "passive"))
      (node (ref "R35") (pin "2") (pinfunction "2_2") (pintype "passive"))
    )
    (net (code "13") (name "Net-(D7-Pad+)") (class "Default")
      (node (ref "D7") (pin "+") (pinfunction "+_+") (pintype "passive"))
      (node (ref "R36") (pin "2") (pinfunction "2_2") (pintype "passive"))
    )
    (net (code "14") (name "Net-(D8-Pad+)") (class "Default")
      (node (ref "D8") (pin "+") (pinfunction "+_+") (pintype "passive"))
      (node (ref "R37") (pin "2") (pinfunction "2_2") (pintype "passive"))
    )
    (net (code "15") (name "Net-(D9-Pad+)") (class "Default")
      (node (ref "D9") (pin "+") (pinfunction "+_+") (pintype "passive"))
      (node (ref "R38") (pin "2") (pinfunction "2_2") (pintype "passive"))
    )
    (net (code "16") (name "Net-(D10-Pad+)") (class "Default")
      (node (ref "D10") (pin "+") (pinfunction "+_+") (pintype "passive"))
      (node (ref "R39") (pin "2") (pinfunction "2_2") (pintype "passive"))
    )
    (net (code "17") (name "Net-(D17-Pad+)") (class "Default")
      (node (ref "D17") (pin "+") (pinfunction "+_+") (pintype "passive"))
      (node (ref "R52") (pin "1") (pinfunction "1_1") (pintype "passive"))
    )
    (net (code "18") (name "Net-(J6-2)") (class "Default")
      (node (ref "J6") (pin "4") (pinfunction "2_4") (pintype "passive"))
      (node (ref "U4") (pin "6") (pinfunction "UD-_6") (pintype "bidirectional"))
    )
    (net (code "19") (name "Net-(Q1-D)") (class "Default")
      (node (ref "Q1") (pin "2") (pinfunction "D_2") (pintype "passive"))
      (node (ref "Q2") (pin "2") (pinfunction "D_2") (pintype "passive"))
      (node (ref "R25") (pin "2") (pinfunction "2_2") (pintype "passive"))
    )
    (net (code "20") (name "Net-(Q1-G)") (class "Default")
      (node (ref "Q1") (pin "1") (pinfunction "G_1") (pintype "passive"))
      (node (ref "R1") (pin "2") (pinfunction "2_2") (pintype "passive"))
      (node (ref "U1") (pin "1") (pinfunction "DSG_1") (pintype "output"))
    )
    (net (code "21") (name "Net-(Q1-S)") (class "Default")
      (node (ref "C13") (pin "1") (pinfunction "1_1") (pintype "passive"))
      (node (ref "Q1") (pin "3") (pinfunction "S_3") (pintype "passive"))
      (node (ref "R1") (pin "1") (pinfunction "1_1") (pintype "passive"))
      (node (ref "R18") (pin "1") (pinfunction "1_1") (pintype "passive"))
      (node (ref "R2") (pin "1") (pinfunction "1_1") (pintype "passive"))
    )
    (net (code "22") (name "Net-(Q2-G)") (class "Default")
      (node (ref "D2") (pin "C") (pinfunction "C_C") (pintype "passive"))
      (node (ref "Q2") (pin "1") (pinfunction "G_1") (pintype "passive"))
      (node (ref "R20") (pin "1") (pinfunction "1_1") (pintype "passive"))
      (node (ref "R21") (pin "2") (pinfunction "2_2") (pintype "passive"))
    )
    (net (code "23") (name "Net-(Q3-D)") (class "Default")
      (node (ref "Q3") (pin "3") (pinfunction "D_3") (pintype "passive"))
      (node (ref "R22") (pin "2") (pinfunction "2_2") (pintype "passive"))
    )
    (net (code "24") (name "Net-(Q3-S)") (class "Default")
      (node (ref "Q3") (pin "2") (pinfunction "S_2") (pintype "passive"))
      (node (ref "U1") (pin "2") (pinfunction "CHG_2") (pintype "output"))
    )
    (net (code "25") (name "Net-(Q4-D)") (class "Default")
      (node (ref "Q4") (pin "3") (pinfunction "D_3") (pintype "passive"))
      (node (ref "R25") (pin "1") (pinfunction "1_1") (pintype "passive"))
    )
    (net (code "26") (name "Net-(Q4-G)") (class "Default")
      (node (ref "Q4") (pin "1") (pinfunction "G_1") (pintype "passive"))
      (node (ref "R23") (pin "2") (pinfunction "2_2") (pintype "passive"))
      (node (ref "R24") (pin "1") (pinfunction "1_1") (pintype "passive"))
    )
    (net (code "27") (name "Net-(Q5-B)") (class "Default")
      (node (ref "Q5") (pin "1") (pinfunction "B_1") (pintype "passive"))
      (node (ref "R26") (pin "1") (pinfunction "1_1") (pintype "passive"))
    )
    (net (code "28") (name "Net-(Q5-C)") (class "Default")
      (node (ref "D5") (pin "A") (pinfunction "A_A") (pintype "passive"))
      (node (ref "Q5") (pin "3") (pinfunction "C_3") (pintype "passive"))
    )
    (net (code "29") (name "Net-(Q6-D)") (class "Default")
      (node (ref "Q6") (pin "3") (pinfunction "D_3") (pintype "passive"))
      (node (ref "R30") (pin "2") (pinfunction "2_2") (pintype "passive"))
    )
    (net (code "30") (name "Net-(Q6-G)") (class "Default")
      (node (ref "Q6") (pin "1") (pinfunction "G_1") (pintype "passive"))
      (node (ref "R28") (pin "2") (pinfunction "2_2") (pintype "passive"))
      (node (ref "R29") (pin "1") (pinfunction "1_1") (pintype "passive"))
    )
    (net (code "31") (name "Net-(Q7-D)") (class "Default")
      (node (ref "Q7") (pin "3") (pinfunction "D_3") (pintype "passive"))
      (node (ref "R28") (pin "1") (pinfunction "1_1") (pintype "passive"))
    )
    (net (code "32") (name "Net-(Q7-G)") (class "Default")
      (node (ref "Q7") (pin "1") (pinfunction "G_1") (pintype "passive"))
      (node (ref "R27") (pin "1") (pinfunction "1_1") (pintype "passive"))
      (node (ref "U2") (pin "12") (pinfunction "VEN_12") (pintype "output"))
    )
    (net (code "33") (name "Net-(Q8-D)") (class "Default")
      (node (ref "Q8") (pin "3") (pinfunction "D_3") (pintype "passive"))
      (node (ref "R15") (pin "1") (pinfunction "1_1") (pintype "passive"))
    )
    (net (code "34") (name "Net-(Q8-G)") (class "Default")
      (node (ref "C8") (pin "1") (pinfunction "1_1") (pintype "passive"))
      (node (ref "D11") (pin "C") (pinfunction "C_C") (pintype "passive"))
      (node (ref "Q8") (pin "1") (pinfunction "G_1") (pintype "passive"))
      (node (ref "R12") (pin "2") (pinfunction "2_2") (pintype "passive"))
      (node (ref "U1") (pin "13") (pinfunction "VC4_13") (pintype "input"))
      (node (ref "U1") (pin "14") (pinfunction "VC3_14") (pintype "input"))
      (node (ref "U1") (pin "15") (pinfunction "VC2_15") (pintype "input"))
    )
    (net (code "35") (name "Net-(Q8-S)") (class "Default")
      (node (ref "D11") (pin "A") (pinfunction "A_A") (pintype "passive"))
      (node (ref "Q8") (pin "2") (pinfunction "S_2") (pintype "passive"))
      (node (ref "R12") (pin "1") (pinfunction "1_1") (pintype "passive"))
      (node (ref "R16") (pin "2") (pinfunction "2_2") (pintype "passive"))
      (node (ref "X1") (pin "3") (pinfunction "S_3") (pintype "passive"))
    )
    (net (code "36") (name "Net-(Q9-D)") (class "Default")
      (node (ref "Q9") (pin "3") (pinfunction "D_3") (pintype "passive"))
      (node (ref "R16") (pin "1") (pinfunction "1_1") (pintype "passive"))
    )
    (net (code "37") (name "Net-(Q9-G)") (class "Default")
      (node (ref "C9") (pin "1") (pinfunction "1_1") (pintype "passive"))
      (node (ref "D12") (pin "C") (pinfunction "C_C") (pintype "passive"))
      (node (ref "Q9") (pin "1") (pinfunction "G_1") (pintype "passive"))
      (node (ref "R13") (pin "2") (pinfunction "2_2") (pintype "passive"))
      (node (ref "U1") (pin "16") (pinfunction "VC1_16") (pintype "input"))
    )
    (net (code "38") (name "Net-(Q10-D)") (class "Default")
      (node (ref "Q10") (pin "3") (pinfunction "D_3") (pintype "passive"))
      (node (ref "R17") (pin "1") (pinfunction "1_1") (pintype "passive"))
    )
    (net (code "39") (name "Net-(Q10-G)") (class "Default")
      (node (ref "C10") (pin "1") (pinfunction "1_1") (pintype "passive"))
      (node (ref "D13") (pin "C") (pinfunction "C_C") (pintype "passive"))
      (node (ref "Q10") (pin "1") (pinfunction "G_1") (pintype "passive"))
      (node (ref "R14") (pin "2") (pinfunction "2_2") (pintype "passive"))
      (node (ref "U1") (pin "17") (pinfunction "VC0_17") (pintype "input"))
    )
    (net (code "40") (name "Net-(Q10-S)") (class "Default")
      (node (ref "D13") (pin "A") (pinfunction "A_A") (pintype "passive"))
      (node (ref "Q10") (pin "2") (pinfunction "S_2") (pintype "passive"))
      (node (ref "R14") (pin "1") (pinfunction "1_1") (pintype "passive"))
      (node (ref "X1") (pin "1") (pinfunction "S_1") (pintype "passive"))
    )
    (net (code "41") (name "Net-(Q13-D)") (class "Default")
      (node (ref "D12") (pin "A") (pinfunction "A_A") (pintype "passive"))
      (node (ref "Q13") (pin "3") (pinfunction "D_3") (pintype "passive"))
      (node (ref "Q9") (pin "2") (pinfunction "S_2") (pintype "passive"))
      (node (ref "R13") (pin "1") (pinfunction "1_1") (pintype "passive"))
      (node (ref "R17") (pin "2") (pinfunction "2_2") (pintype "passive"))
      (node (ref "S1") (pin "1") (pinfunction "1.1_1") (pintype "passive"))
      (node (ref "S1") (pin "2") (pinfunction "1.2_2") (pintype "passive"))
      (node (ref "X1") (pin "2") (pinfunction "S_2") (pintype "passive"))
    )
    (net (code "42") (name "Net-(Q13-S)") (class "Default")
      (node (ref "Q13") (pin "2") (pinfunction "S_2") (pintype "passive"))
      (node (ref "R8") (pin "2") (pinfunction "2_2") (pintype "passive"))
      (node (ref "S1") (pin "3") (pinfunction "2.1_3") (pintype "passive"))
      (node (ref "S1") (pin "4") (pinfunction "2.2_4") (pintype "passive"))
    )
    (net (code "43") (name "Net-(S2-2.1)") (class "Default")
      (node (ref "R33") (pin "1") (pinfunction "1_1") (pintype "passive"))
      (node (ref "S2") (pin "3") (pinfunction "2.1_3") (pintype "passive"))
      (node (ref "S2") (pin "4") (pinfunction "2.2_4") (pintype "passive"))
      (node (ref "U2") (pin "14") (pinfunction "~{DISP}_14") (pintype "input"))
    )
    (net (code "44") (name "Net-(S3-2.1)") (class "Default")
      (node (ref "C22") (pin "2") (pinfunction "2_2") (pintype "passive"))
      (node (ref "R34") (pin "1") (pinfunction "1_1") (pintype "passive"))
      (node (ref "S3") (pin "3") (pinfunction "2.1_3") (pintype "passive"))
      (node (ref "S3") (pin "4") (pinfunction "2.2_4") (pintype "passive"))
      (node (ref "U3") (pin "29") (pinfunction "PC6(/RESET)_29") (pintype "bidirectional"))
    )
    (net (code "45") (name "Net-(U1-BAT)") (class "Default")
      (node (ref "C6") (pin "2") (pinfunction "2_2") (pintype "passive"))
      (node (ref "R9") (pin "2") (pinfunction "2_2") (pintype "passive"))
      (node (ref "U1") (pin "10") (pinfunction "BAT_10") (pintype "power_in"))
      (node (ref "U1") (pin "9") (pinfunction "REGSRC_9") (pintype "input"))
    )
    (net (code "46") (name "Net-(U1-CAP1)") (class "Default")
      (node (ref "C4") (pin "1") (pinfunction "1_1") (pintype "passive"))
      (node (ref "U1") (pin "7") (pinfunction "CAP1_7") (pintype "output"))
    )
    (net (code "47") (name "Net-(U1-SRN)") (class "Default")
      (node (ref "C1") (pin "1") (pinfunction "1_1") (pintype "passive"))
      (node (ref "C2") (pin "2") (pinfunction "2_2") (pintype "passive"))
      (node (ref "R2") (pin "2") (pinfunction "2_2") (pintype "passive"))
      (node (ref "U1") (pin "19") (pinfunction "SRN_19") (pintype "input"))
    )
    (net (code "48") (name "Net-(U1-SRP)") (class "Default")
      (node (ref "C2") (pin "1") (pinfunction "1_1") (pintype "passive"))
      (node (ref "C3") (pin "2") (pinfunction "2_2") (pintype "passive"))
      (node (ref "R3") (pin "2") (pinfunction "2_2") (pintype "passive"))
      (node (ref "U1") (pin "18") (pinfunction "SRP_18") (pintype "input"))
    )
    (net (code "49") (name "Net-(U1-TS1)") (class "Default")
      (node (ref "C25") (pin "1") (pinfunction "1_1") (pintype "passive"))
      (node (ref "R7") (pin "2") (pinfunction "2_2") (pintype "passive"))
      (node (ref "R8") (pin "1") (pinfunction "1_1") (pintype "passive"))
      (node (ref "U1") (pin "6") (pinfunction "TS1_6") (pintype "input"))
    )
    (net (code "50") (name "Net-(U1-VC5)") (class "Default")
      (node (ref "C7") (pin "1") (pinfunction "1_1") (pintype "passive"))
      (node (ref "R11") (pin "2") (pinfunction "2_2") (pintype "passive"))
      (node (ref "U1") (pin "12") (pinfunction "VC5_12") (pintype "input"))
    )
    (net (code "51") (name "Net-(U2A-BAT)") (class "Default")
      (node (ref "C16") (pin "1") (pinfunction "1_1") (pintype "passive"))
      (node (ref "R30") (pin "1") (pinfunction "1_1") (pintype "passive"))
      (node (ref "R31") (pin "2") (pinfunction "2_2") (pintype "passive"))
      (node (ref "U2") (pin "7") (pinfunction "BAT_7") (pintype "input"))
    )
    (net (code "52") (name "Net-(U2A-LED1)") (class "Default")
      (node (ref "D6") (pin "-") (pinfunction "-_-") (pintype "passive"))
      (node (ref "U2") (pin "16") (pinfunction "LED1_16") (pintype "output"))
    )
    (net (code "53") (name "Net-(U2A-LED2)") (class "Default")
      (node (ref "D7") (pin "-") (pinfunction "-_-") (pintype "passive"))
      (node (ref "U2") (pin "17") (pinfunction "LED2_17") (pintype "output"))
    )
    (net (code "54") (name "Net-(U2A-LED3)") (class "Default")
      (node (ref "D8") (pin "-") (pinfunction "-_-") (pintype "passive"))
      (node (ref "U2") (pin "18") (pinfunction "LED3_18") (pintype "output"))
    )
    (net (code "55") (name "Net-(U2A-LED4)") (class "Default")
      (node (ref "D9") (pin "-") (pinfunction "-_-") (pintype "passive"))
      (node (ref "U2") (pin "19") (pinfunction "LED4_19") (pintype "output"))
    )
    (net (code "56") (name "Net-(U2A-LED5)") (class "Default")
      (node (ref "D10") (pin "-") (pinfunction "-_-") (pintype "passive"))
      (node (ref "U2") (pin "20") (pinfunction "LED5_20") (pintype "output"))
    )
    (net (code "57") (name "Net-(U2A-RBI)") (class "Default")
      (node (ref "C15") (pin "1") (pinfunction "1_1") (pintype "passive"))
      (node (ref "U2") (pin "27") (pinfunction "RBI_27") (pintype "input"))
    )
    (net (code "58") (name "Net-(U2A-~{MRST})") (class "Default")
      (node (ref "R32") (pin "1") (pinfunction "1_1") (pintype "passive"))
      (node (ref "U2") (pin "24") (pinfunction "~{MRST}_24") (pintype "input"))
    )
    (net (code "59") (name "Net-(U3-AREF)") (class "Default")
      (node (ref "C23") (pin "2") (pinfunction "2_2") (pintype "passive"))
      (node (ref "U3") (pin "20") (pinfunction "AREF_20") (pintype "bidirectional"))
    )
    (net (code "60") (name "Net-(U3-PB6(XTAL1{slash}TOSC1))") (class "Default")
      (node (ref "U3") (pin "7") (pinfunction "PB6(XTAL1/TOSC1)_7") (pintype "bidirectional"))
      (node (ref "Y2") (pin "1") (pinfunction "1_1") (pintype "passive"))
    )
    (net (code "61") (name "Net-(U3-PB7(XTAL2{slash}TOSC2))") (class "Default")
      (node (ref "U3") (pin "8") (pinfunction "PB7(XTAL2/TOSC2)_8") (pintype "bidirectional"))
      (node (ref "Y2") (pin "3") (pinfunction "3_3") (pintype "passive"))
    )
    (net (code "62") (name "Net-(U3-PD0(RXD))") (class "Default")
      (node (ref "R46") (pin "2") (pinfunction "2_2") (pintype "passive"))
      (node (ref "U3") (pin "30") (pinfunction "PD0(RXD)_30") (pintype "bidirectional"))
    )
    (net (code "63") (name "Net-(U3-PD1(TXD))") (class "Default")
      (node (ref "R45") (pin "2") (pinfunction "2_2") (pintype "passive"))
      (node (ref "U3") (pin "31") (pinfunction "PD1(TXD)_31") (pintype "bidirectional"))
    )
    (net (code "64") (name "Net-(U3-PD5(T1))") (class "Default")
      (node (ref "R52") (pin "2") (pinfunction "2_2") (pintype "passive"))
      (node (ref "U3") (pin "9") (pinfunction "PD5(T1)_9") (pintype "bidirectional"))
    )
    (net (code "65") (name "Net-(U4-RXD)") (class "Default")
      (node (ref "R45") (pin "1") (pinfunction "1_1") (pintype "passive"))
      (node (ref "U4") (pin "3") (pinfunction "RXD_3") (pintype "bidirectional"))
    )
    (net (code "66") (name "Net-(U4-TXD)") (class "Default")
      (node (ref "R46") (pin "1") (pinfunction "1_1") (pintype "passive"))
      (node (ref "U4") (pin "2") (pinfunction "TXD_2") (pintype "bidirectional"))
    )
    (net (code "67") (name "Net-(U4-UD+)") (class "Default")
      (node (ref "J6") (pin "3") (pinfunction "3_3") (pintype "passive"))
      (node (ref "U4") (pin "5") (pinfunction "UD+_5") (pintype "bidirectional"))
    )
    (net (code "68") (name "Net-(U4-XI)") (class "Default")
      (node (ref "U4") (pin "7") (pinfunction "XI_7") (pintype "bidirectional"))
      (node (ref "Y1") (pin "1") (pinfunction "1_1") (pintype "passive"))
    )
    (net (code "69") (name "Net-(U4-XO)") (class "Default")
      (node (ref "U4") (pin "8") (pinfunction "XO_8") (pintype "bidirectional"))
      (node (ref "Y1") (pin "3") (pinfunction "3_3") (pintype "passive"))
    )
    (net (code "70") (name "Net-(U4-~{DTR})") (class "Default")
      (node (ref "C22") (pin "1") (pinfunction "1_1") (pintype "passive"))
      (node (ref "U4") (pin "13") (pinfunction "~{DTR}_13") (pintype "bidirectional"))
    )
    (net (code "71") (name "Net-(U5-SW)") (class "Default")
      (node (ref "C19") (pin "2") (pinfunction "2_2") (pintype "passive"))
      (node (ref "L1") (pin "2") (pinfunction "2_2") (pintype "passive"))
      (node (ref "U5") (pin "2") (pinfunction "SW_2") (pintype "passive"))
    )
    (net (code "72") (name "Net-(U5-VBST)") (class "Default")
      (node (ref "C19") (pin "1") (pinfunction "1_1") (pintype "passive"))
      (node (ref "U5") (pin "6") (pinfunction "VBST_6") (pintype "input"))
    )
    (net (code "73") (name "Net-(U5-VFB)") (class "Default")
      (node (ref "R50") (pin "2") (pinfunction "2_2") (pintype "passive"))
      (node (ref "R51") (pin "1") (pinfunction "1_1") (pintype "passive"))
      (node (ref "U5") (pin "4") (pinfunction "VFB_4") (pintype "input"))
    )
    (net (code "74") (name "PACK-") (class "Default")
      (node (ref "C11") (pin "2") (pinfunction "2_2") (pintype "passive"))
      (node (ref "C14") (pin "2") (pinfunction "2_2") (pintype "passive"))
      (node (ref "D4") (pin "A") (pinfunction "A_A") (pintype "passive"))
      (node (ref "J2") (pin "-") (pinfunction "-_-") (pintype "passive"))
      (node (ref "Q2") (pin "3") (pinfunction "S_3") (pintype "passive"))
      (node (ref "Q4") (pin "2") (pinfunction "S_2") (pintype "passive"))
      (node (ref "R21") (pin "1") (pinfunction "1_1") (pintype "passive"))
      (node (ref "R23") (pin "1") (pinfunction "1_1") (pintype "passive"))
    )
    (net (code "75") (name "PRECHG") (class "Default")
      (node (ref "R26") (pin "2") (pinfunction "2_2") (pintype "passive"))
      (node (ref "U2") (pin "5") (pinfunction "~{PRECHG}_5") (pintype "output"))
    )
    (net (code "76") (name "REGOUT") (class "Default")
      (node (ref "C17") (pin "1") (pinfunction "1_1") (pintype "passive"))
      (node (ref "C5") (pin "1") (pinfunction "1_1") (pintype "passive"))
      (node (ref "Q11") (pin "1") (pinfunction "G_1") (pintype "passive"))
      (node (ref "Q12") (pin "1") (pinfunction "G_1") (pintype "passive"))
      (node (ref "Q5") (pin "2") (pinfunction "E_2") (pintype "passive"))
      (node (ref "R27") (pin "2") (pinfunction "2_2") (pintype "passive"))
      (node (ref "R32") (pin "2") (pinfunction "2_2") (pintype "passive"))
      (node (ref "R33") (pin "2") (pinfunction "2_2") (pintype "passive"))
      (node (ref "R35") (pin "1") (pinfunction "1_1") (pintype "passive"))
      (node (ref "R36") (pin "1") (pinfunction "1_1") (pintype "passive"))
      (node (ref "R37") (pin "1") (pinfunction "1_1") (pintype "passive"))
      (node (ref "R38") (pin "1") (pinfunction "1_1") (pintype "passive"))
      (node (ref "R39") (pin "1") (pinfunction "1_1") (pintype "passive"))
      (node (ref "R4") (pin "2") (pinfunction "2_2") (pintype "passive"))
      (node (ref "R41") (pin "2") (pinfunction "2_2") (pintype "passive"))
      (node (ref "R43") (pin "2") (pinfunction "2_2") (pintype "passive"))
      (node (ref "R5") (pin "2") (pinfunction "2_2") (pintype "passive"))
      (node (ref "REGOUT") (pin "TP") (pinfunction "PP_TP") (pintype "input"))
      (node (ref "U1") (pin "8") (pinfunction "REGOUT_8") (pintype "power_in"))
      (node (ref "U2") (pin "26") (pinfunction "VCC_26") (pintype "power_in"))
    )
    (net (code "77") (name "SCL") (class "Default")
      (node (ref "R5") (pin "1") (pinfunction "1_1") (pintype "passive"))
      (node (ref "U1") (pin "5") (pinfunction "SCL_5") (pintype "input"))
      (node (ref "U2") (pin "4") (pinfunction "SCL_4") (pintype "bidirectional"))
    )
    (net (code "78") (name "SDA") (class "Default")
      (node (ref "R4") (pin "1") (pinfunction "1_1") (pintype "passive"))
      (node (ref "U1") (pin "4") (pinfunction "SDA_4") (pintype "bidirectional"))
      (node (ref "U2") (pin "3") (pinfunction "SDA_3") (pintype "bidirectional"))
    )
    (net (code "79") (name "SMBC") (class "Default")
      (node (ref "Q11") (pin "2") (pinfunction "S_2") (pintype "passive"))
      (node (ref "R43") (pin "1") (pinfunction "1_1") (pintype "passive"))
      (node (ref "U2") (pin "13") (pinfunction "SMBC_13") (pintype "bidirectional"))
      (node (ref "X2") (pin "3") (pinfunction "S_3") (pintype "passive"))
    )
    (net (code "80") (name "SMBC_MCU") (class "Default")
      (node (ref "Q11") (pin "3") (pinfunction "D_3") (pintype "passive"))
      (node (ref "R44") (pin "1") (pinfunction "1_1") (pintype "passive"))
      (node (ref "U3") (pin "28") (pinfunction "PC5(ADC5/SCL)_28") (pintype "bidirectional"))
    )
    (net (code "81") (name "SMBD") (class "Default")
      (node (ref "Q12") (pin "2") (pinfunction "S_2") (pintype "passive"))
      (node (ref "R41") (pin "1") (pinfunction "1_1") (pintype "passive"))
      (node (ref "U2") (pin "11") (pinfunction "SMBD_11") (pintype "bidirectional"))
      (node (ref "X2") (pin "2") (pinfunction "S_2") (pintype "passive"))
    )
    (net (code "82") (name "SMBD_MCU") (class "Default")
      (node (ref "Q12") (pin "3") (pinfunction "D_3") (pintype "passive"))
      (node (ref "R42") (pin "1") (pinfunction "1_1") (pintype "passive"))
      (node (ref "U3") (pin "27") (pinfunction "PC4(ADC4/SDA)_27") (pintype "bidirectional"))
    )
    (net (code "83") (name "USB+") (class "Default")
      (node (ref "C20") (pin "A") (pinfunction "+_A") (pintype "passive"))
      (node (ref "C21") (pin "1") (pinfunction "1_1") (pintype "passive"))
      (node (ref "D14") (pin "A") (pinfunction "A_A") (pintype "passive"))
      (node (ref "J6") (pin "5") (pinfunction "1_5") (pintype "passive"))
      (node (ref "U4") (pin "16") (pinfunction "VCC_16") (pintype "bidirectional"))
    )
    (net (code "84") (name "unconnected-(J6-4-Pad2)") (class "Default")
      (node (ref "J6") (pin "2") (pinfunction "4_2") (pintype "passive"))
    )
    (net (code "85") (name "unconnected-(S1-SH-Pad5)") (class "Default")
      (node (ref "S1") (pin "5") (pinfunction "SH_5") (pintype "passive"))
    )
    (net (code "86") (name "unconnected-(S2-SH-Pad5)") (class "Default")
      (node (ref "S2") (pin "5") (pinfunction "SH_5") (pintype "passive"))
    )
    (net (code "87") (name "unconnected-(S3-SH-Pad5)") (class "Default")
      (node (ref "S3") (pin "5") (pinfunction "SH_5") (pintype "passive"))
    )
    (net (code "88") (name "unconnected-(U1-NC-Pad11)") (class "Default")
      (node (ref "U1") (pin "11") (pinfunction "NC_11") (pintype "no_connect"))
    )
    (net (code "89") (name "unconnected-(U2A-ADREN-Pad29)") (class "Default")
      (node (ref "U2") (pin "29") (pinfunction "ADREN_29") (pintype "output"))
    )
    (net (code "90") (name "unconnected-(U2A-COM-Pad1)") (class "Default")
      (node (ref "U2") (pin "1") (pinfunction "COM_1") (pintype "output"))
    )
    (net (code "91") (name "unconnected-(U2A-PWRM-Pad15)") (class "Default")
      (node (ref "U2") (pin "15") (pinfunction "PWRM_15") (pintype "output"))
    )
    (net (code "92") (name "unconnected-(U2A-SAFE-Pad10)") (class "Default")
      (node (ref "U2") (pin "10") (pinfunction "SAFE_10") (pintype "output"))
    )
    (net (code "93") (name "unconnected-(U3-ADC6-Pad19)") (class "Default")
      (node (ref "U3") (pin "19") (pinfunction "ADC6_19") (pintype "bidirectional"))
    )
    (net (code "94") (name "unconnected-(U3-ADC7-Pad22)") (class "Default")
      (node (ref "U3") (pin "22") (pinfunction "ADC7_22") (pintype "bidirectional"))
    )
    (net (code "95") (name "unconnected-(U3-PB0(ICP)-Pad12)") (class "Default")
      (node (ref "U3") (pin "12") (pinfunction "PB0(ICP)_12") (pintype "bidirectional"))
    )
    (net (code "96") (name "unconnected-(U3-PB1(OC1A)-Pad13)") (class "Default")
      (node (ref "U3") (pin "13") (pinfunction "PB1(OC1A)_13") (pintype "bidirectional"))
    )
    (net (code "97") (name "unconnected-(U3-PB2(SS{slash}OC1B)-Pad14)") (class "Default")
      (node (ref "U3") (pin "14") (pinfunction "PB2(SS/OC1B)_14") (pintype "bidirectional"))
    )
    (net (code "98") (name "unconnected-(U3-PB3(MOSI{slash}OC2)-Pad15)") (class "Default")
      (node (ref "U3") (pin "15") (pinfunction "PB3(MOSI/OC2)_15") (pintype "bidirectional"))
    )
    (net (code "99") (name "unconnected-(U3-PB4(MISO)-Pad16)") (class "Default")
      (node (ref "U3") (pin "16") (pinfunction "PB4(MISO)_16") (pintype "bidirectional"))
    )
    (net (code "100") (name "unconnected-(U3-PB5(SCK)-Pad17)") (class "Default")
      (node (ref "U3") (pin "17") (pinfunction "PB5(SCK)_17") (pintype "bidirectional"))
    )
    (net (code "101") (name "unconnected-(U3-PC0(ADC0)-Pad23)") (class "Default")
      (node (ref "U3") (pin "23") (pinfunction "PC0(ADC0)_23") (pintype "bidirectional"))
    )
    (net (code "102") (name "unconnected-(U3-PC1(ADC1)-Pad24)") (class "Default")
      (node (ref "U3") (pin "24") (pinfunction "PC1(ADC1)_24") (pintype "bidirectional"))
    )
    (net (code "103") (name "unconnected-(U3-PC2(ADC2)-Pad25)") (class "Default")
      (node (ref "U3") (pin "25") (pinfunction "PC2(ADC2)_25") (pintype "bidirectional"))
    )
    (net (code "104") (name "unconnected-(U3-PC3(ADC3)-Pad26)") (class "Default")
      (node (ref "U3") (pin "26") (pinfunction "PC3(ADC3)_26") (pintype "bidirectional"))
    )
    (net (code "105") (name "unconnected-(U3-PD2(INT0)-Pad32)") (class "Default")
      (node (ref "U3") (pin "32") (pinfunction "PD2(INT0)_32") (pintype "bidirectional"))
    )
    (net (code "106") (name "unconnected-(U3-PD4(XCK{slash}T0)-Pad2)") (class "Default")
      (node (ref "U3") (pin "2") (pinfunction "PD4(XCK/T0)_2") (pintype "bidirectional"))
    )
    (net (code "107") (name "unconnected-(U3-PD6(AIN0)-Pad10)") (class "Default")
      (node (ref "U3") (pin "10") (pinfunction "PD6(AIN0)_10") (pintype "bidirectional"))
    )
    (net (code "108") (name "unconnected-(U3-PD7(AIN1)-Pad11)") (class "Default")
      (node (ref "U3") (pin "11") (pinfunction "PD7(AIN1)_11") (pintype "bidirectional"))
    )
    (net (code "109") (name "unconnected-(U4-R232-Pad15)") (class "Default")
      (node (ref "U4") (pin "15") (pinfunction "R232_15") (pintype "bidirectional"))
    )
    (net (code "110") (name "unconnected-(U4-V3-Pad4)") (class "Default")
      (node (ref "U4") (pin "4") (pinfunction "V3_4") (pintype "bidirectional"))
    )
    (net (code "111") (name "unconnected-(U4-~{CTS}-Pad9)") (class "Default")
      (node (ref "U4") (pin "9") (pinfunction "~{CTS}_9") (pintype "bidirectional"))
    )
    (net (code "112") (name "unconnected-(U4-~{DCD}-Pad12)") (class "Default")
      (node (ref "U4") (pin "12") (pinfunction "~{DCD}_12") (pintype "bidirectional"))
    )
    (net (code "113") (name "unconnected-(U4-~{DSR}-Pad10)") (class "Default")
      (node (ref "U4") (pin "10") (pinfunction "~{DSR}_10") (pintype "bidirectional"))
    )
    (net (code "114") (name "unconnected-(U4-~{RI}-Pad11)") (class "Default")
      (node (ref "U4") (pin "11") (pinfunction "~{RI}_11") (pintype "bidirectional"))
    )
    (net (code "115") (name "unconnected-(U4-~{RTS}-Pad14)") (class "Default")
      (node (ref "U4") (pin "14") (pinfunction "~{RTS}_14") (pintype "bidirectional"))
    )
    (net (code "116") (name "unconnected-(X2A-S-Pad1)") (class "Default")
      (node (ref "X2") (pin "1") (pinfunction "S_1") (pintype "passive"))
    )
  )
)
